# garage-door-opener.net
KiCad netlist of a schematic drawn in EAGLE
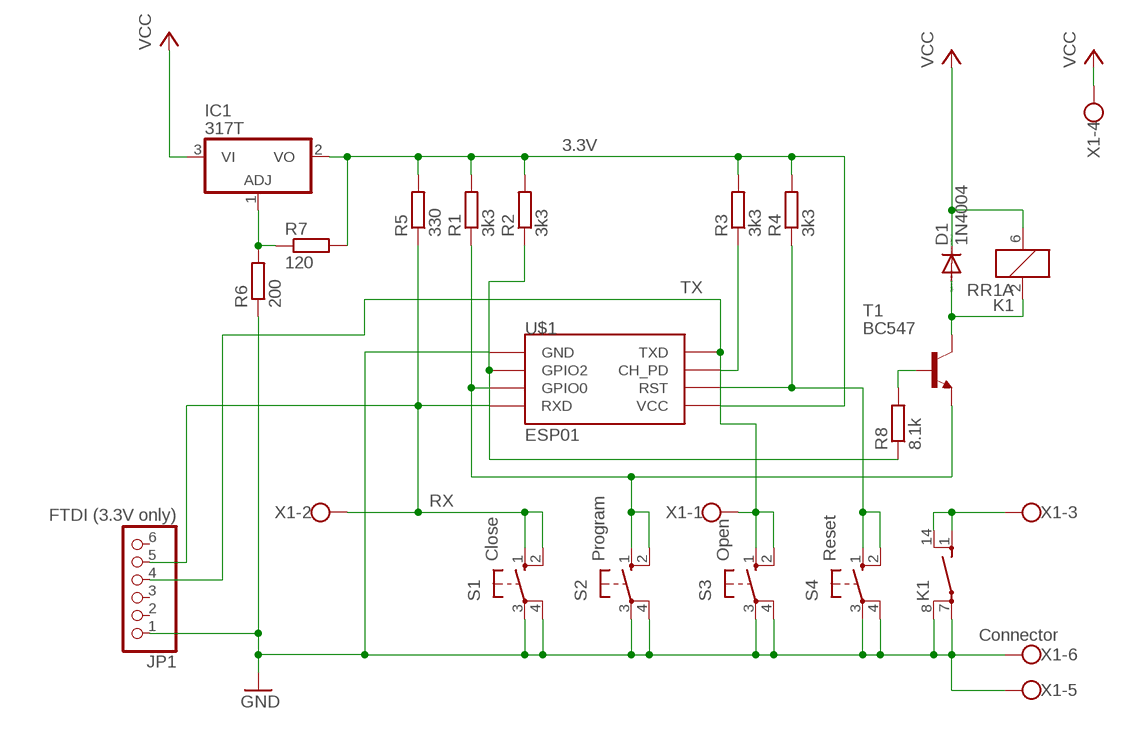
[diagram p0: schematic, sheet 1]

(export (version "E")
  (design (tool "Eeschema 10.0.6"))
  (components
    (comp (ref "D1")
      (value "1N4004")
      (footprint "eagle-import:DO41-10")
      (libsource (lib "eagle-import") (part "1N4004"))
    )
    (comp (ref "IC1")
      (value "317T")
      (footprint "eagle-import:TO220H")
      (libsource (lib "eagle-import") (part "317T"))
    )
    (comp (ref "JP1")
      (value "FTDI (3.3V only)")
      (footprint "eagle-import:1X06")
      (libsource (lib "eagle-import") (part "PINHD-1X6"))
    )
    (comp (ref "K1")
      (value "RR1A")
      (footprint "eagle-import:RR1A")
      (libsource (lib "eagle-import") (part "RR1A"))
    )
    (comp (ref "R1")
      (value "3k3")
      (footprint "eagle-import:0204_7")
      (libsource (lib "eagle-import") (part "R-EU_0204/7"))
    )
    (comp (ref "R2")
      (value "3k3")
      (footprint "eagle-import:0204_7")
      (libsource (lib "eagle-import") (part "R-EU_0204/7"))
    )
    (comp (ref "R3")
      (value "3k3")
      (footprint "eagle-import:0204_7")
      (libsource (lib "eagle-import") (part "R-EU_0204/7"))
    )
    (comp (ref "R4")
      (value "3k3")
      (footprint "eagle-import:0204_7")
      (libsource (lib "eagle-import") (part "R-EU_0204/7"))
    )
    (comp (ref "R5")
      (value "330")
      (footprint "eagle-import:0204_7")
      (libsource (lib "eagle-import") (part "R-EU_0204/7"))
    )
    (comp (ref "R6")
      (value "200")
      (footprint "eagle-import:0204_7")
      (libsource (lib "eagle-import") (part "R-EU_0204/7"))
    )
    (comp (ref "R7")
      (value "120")
      (footprint "eagle-import:0204_7")
      (libsource (lib "eagle-import") (part "R-EU_0204/7"))
    )
    (comp (ref "R8")
      (value "8.1k")
      (footprint "eagle-import:0204_7")
      (libsource (lib "eagle-import") (part "R-EU_0204/7"))
    )
    (comp (ref "S1")
      (value "Close")
      (footprint "eagle-import:B3F-10XX")
      (fields (field (name "MPN") "B3F-1000"))
      (libsource (lib "eagle-import") (part "10-XX"))
    )
    (comp (ref "S2")
      (value "Program")
      (footprint "eagle-import:B3F-10XX")
      (fields (field (name "MPN") "B3F-1000"))
      (libsource (lib "eagle-import") (part "10-XX"))
    )
    (comp (ref "S3")
      (value "Open")
      (footprint "eagle-import:B3F-10XX")
      (fields (field (name "MPN") "B3F-1000"))
      (libsource (lib "eagle-import") (part "10-XX"))
    )
    (comp (ref "S4")
      (value "Reset")
      (footprint "eagle-import:B3F-10XX")
      (fields (field (name "MPN") "B3F-1000"))
      (libsource (lib "eagle-import") (part "10-XX"))
    )
    (comp (ref "T1")
      (value "BC547")
      (footprint "eagle-import:TO92")
      (libsource (lib "eagle-import") (part "BC547"))
    )
    (comp (ref "U$1")
      (value "ESP01")
      (footprint "eagle-import:ESP01")
      (libsource (lib "eagle-import") (part "ESP01"))
    )
    (comp (ref "X1")
      (value "Connector")
      (footprint "eagle-import:W237-6")
      (libsource (lib "eagle-import") (part "W237-6"))
    )
  )
  (nets
    (net (code "1") (name "/3.3V") (class "Default")
      (node (ref "IC1") (pin "2") (pinfunction "VO_2") (pintype "passive"))
      (node (ref "R1") (pin "2") (pinfunction "2_2") (pintype "passive"))
      (node (ref "R2") (pin "2") (pinfunction "2_2") (pintype "passive"))
      (node (ref "R3") (pin "2") (pinfunction "2_2") (pintype "passive"))
      (node (ref "R4") (pin "2") (pinfunction "2_2") (pintype "passive"))
      (node (ref "R5") (pin "2") (pinfunction "2_2") (pintype "passive"))
      (node (ref "R7") (pin "2") (pinfunction "2_2") (pintype "passive"))
      (node (ref "U$1") (pin "VCC") (pinfunction "VCC_VCC") (pintype "bidirectional"))
    )
    (net (code "2") (name "/RX") (class "Default")
      (node (ref "JP1") (pin "5") (pinfunction "5_5") (pintype "passive"))
      (node (ref "R5") (pin "1") (pinfunction "1_1") (pintype "passive"))
      (node (ref "S1") (pin "1") (pinfunction "S_1") (pintype "passive"))
      (node (ref "S1") (pin "2") (pinfunction "S1_2") (pintype "passive"))
      (node (ref "U$1") (pin "RX") (pinfunction "RXD_RX") (pintype "bidirectional"))
      (node (ref "X1") (pin "2") (pinfunction "KL_2") (pintype "passive"))
    )
    (net (code "3") (name "/TX") (class "Default")
      (node (ref "JP1") (pin "4") (pinfunction "4_4") (pintype "passive"))
      (node (ref "S3") (pin "1") (pinfunction "S_1") (pintype "passive"))
      (node (ref "S3") (pin "2") (pinfunction "S1_2") (pintype "passive"))
      (node (ref "U$1") (pin "TX") (pinfunction "TXD_TX") (pintype "bidirectional"))
      (node (ref "X1") (pin "1") (pinfunction "KL_1") (pintype "passive"))
    )
    (net (code "4") (name "GND") (class "Default")
      (node (ref "JP1") (pin "1") (pinfunction "1_1") (pintype "passive"))
      (node (ref "K1") (pin "7") (pinfunction "P_7") (pintype "passive"))
      (node (ref "K1") (pin "8") (pinfunction "P_8") (pintype "passive"))
      (node (ref "R6") (pin "1") (pinfunction "1_1") (pintype "passive"))
      (node (ref "S1") (pin "3") (pinfunction "P_3") (pintype "passive"))
      (node (ref "S1") (pin "4") (pinfunction "P1_4") (pintype "passive"))
      (node (ref "S2") (pin "3") (pinfunction "P_3") (pintype "passive"))
      (node (ref "S2") (pin "4") (pinfunction "P1_4") (pintype "passive"))
      (node (ref "S3") (pin "3") (pinfunction "P_3") (pintype "passive"))
      (node (ref "S3") (pin "4") (pinfunction "P1_4") (pintype "passive"))
      (node (ref "S4") (pin "3") (pinfunction "P_3") (pintype "passive"))
      (node (ref "S4") (pin "4") (pinfunction "P1_4") (pintype "passive"))
      (node (ref "U$1") (pin "GND") (pinfunction "GND_GND") (pintype "bidirectional"))
      (node (ref "X1") (pin "5") (pinfunction "KL_5") (pintype "passive"))
      (node (ref "X1") (pin "6") (pinfunction "KL_6") (pintype "passive"))
    )
    (net (code "5") (name "Net-(IC1-ADJ)") (class "Default")
      (node (ref "IC1") (pin "1") (pinfunction "ADJ_1") (pintype "input"))
      (node (ref "R6") (pin "2") (pinfunction "2_2") (pintype "passive"))
      (node (ref "R7") (pin "1") (pinfunction "1_1") (pintype "passive"))
    )
    (net (code "6") (name "Net-(K1A-1)") (class "Default")
      (node (ref "D1") (pin "A") (pinfunction "A_A") (pintype "passive"))
      (node (ref "K1") (pin "2") (pinfunction "1_2") (pintype "passive"))
      (node (ref "T1") (pin "3") (pinfunction "C_3") (pintype "passive"))
    )
    (net (code "7") (name "Net-(R2-Pad1)") (class "Default")
      (node (ref "R2") (pin "1") (pinfunction "1_1") (pintype "passive"))
      (node (ref "R8") (pin "1") (pinfunction "1_1") (pintype "passive"))
      (node (ref "U$1") (pin "GPIO2") (pinfunction "GPIO2_GPIO2") (pintype "bidirectional"))
    )
    (net (code "8") (name "Net-(R3-Pad1)") (class "Default")
      (node (ref "R3") (pin "1") (pinfunction "1_1") (pintype "passive"))
      (node (ref "U$1") (pin "CH_PD") (pinfunction "CH_PD_CH_PD") (pintype "bidirectional"))
    )
    (net (code "9") (name "Net-(S2-S)") (class "Default")
      (node (ref "R1") (pin "1") (pinfunction "1_1") (pintype "passive"))
      (node (ref "S2") (pin "1") (pinfunction "S_1") (pintype "passive"))
      (node (ref "S2") (pin "2") (pinfunction "S1_2") (pintype "passive"))
      (node (ref "T1") (pin "1") (pinfunction "E_1") (pintype "passive"))
      (node (ref "U$1") (pin "GPIO0") (pinfunction "GPIO0_GPIO0") (pintype "bidirectional"))
    )
    (net (code "10") (name "Net-(S4-S)") (class "Default")
      (node (ref "R4") (pin "1") (pinfunction "1_1") (pintype "passive"))
      (node (ref "S4") (pin "1") (pinfunction "S_1") (pintype "passive"))
      (node (ref "S4") (pin "2") (pinfunction "S1_2") (pintype "passive"))
      (node (ref "U$1") (pin "RST") (pinfunction "RST_RST") (pintype "bidirectional"))
    )
    (net (code "11") (name "Net-(T1-B)") (class "Default")
      (node (ref "R8") (pin "2") (pinfunction "2_2") (pintype "passive"))
      (node (ref "T1") (pin "2") (pinfunction "B_2") (pintype "passive"))
    )
    (net (code "12") (name "Net-(X1C-KL)") (class "Default")
      (node (ref "K1") (pin "1") (pinfunction "S_1") (pintype "passive"))
      (node (ref "K1") (pin "14") (pinfunction "S_14") (pintype "passive"))
      (node (ref "X1") (pin "3") (pinfunction "KL_3") (pintype "passive"))
    )
    (net (code "13") (name "VCC") (class "Default")
      (node (ref "D1") (pin "C") (pinfunction "C_C") (pintype "passive"))
      (node (ref "IC1") (pin "3") (pinfunction "VI_3") (pintype "input"))
      (node (ref "K1") (pin "6") (pinfunction "2_6") (pintype "passive"))
      (node (ref "X1") (pin "4") (pinfunction "KL_4") (pintype "passive"))
    )
    (net (code "14") (name "unconnected-(JP1-Pad2)") (class "Default")
      (node (ref "JP1") (pin "2") (pinfunction "2_2") (pintype "passive"))
    )
    (net (code "15") (name "unconnected-(JP1-Pad3)") (class "Default")
      (node (ref "JP1") (pin "3") (pinfunction "3_3") (pintype "passive"))
    )
    (net (code "16") (name "unconnected-(JP1-Pad6)") (class "Default")
      (node (ref "JP1") (pin "6") (pinfunction "6_6") (pintype "passive"))
    )
  )
)
